# schematic.net
KiCad netlist of a schematic drawn in EAGLE
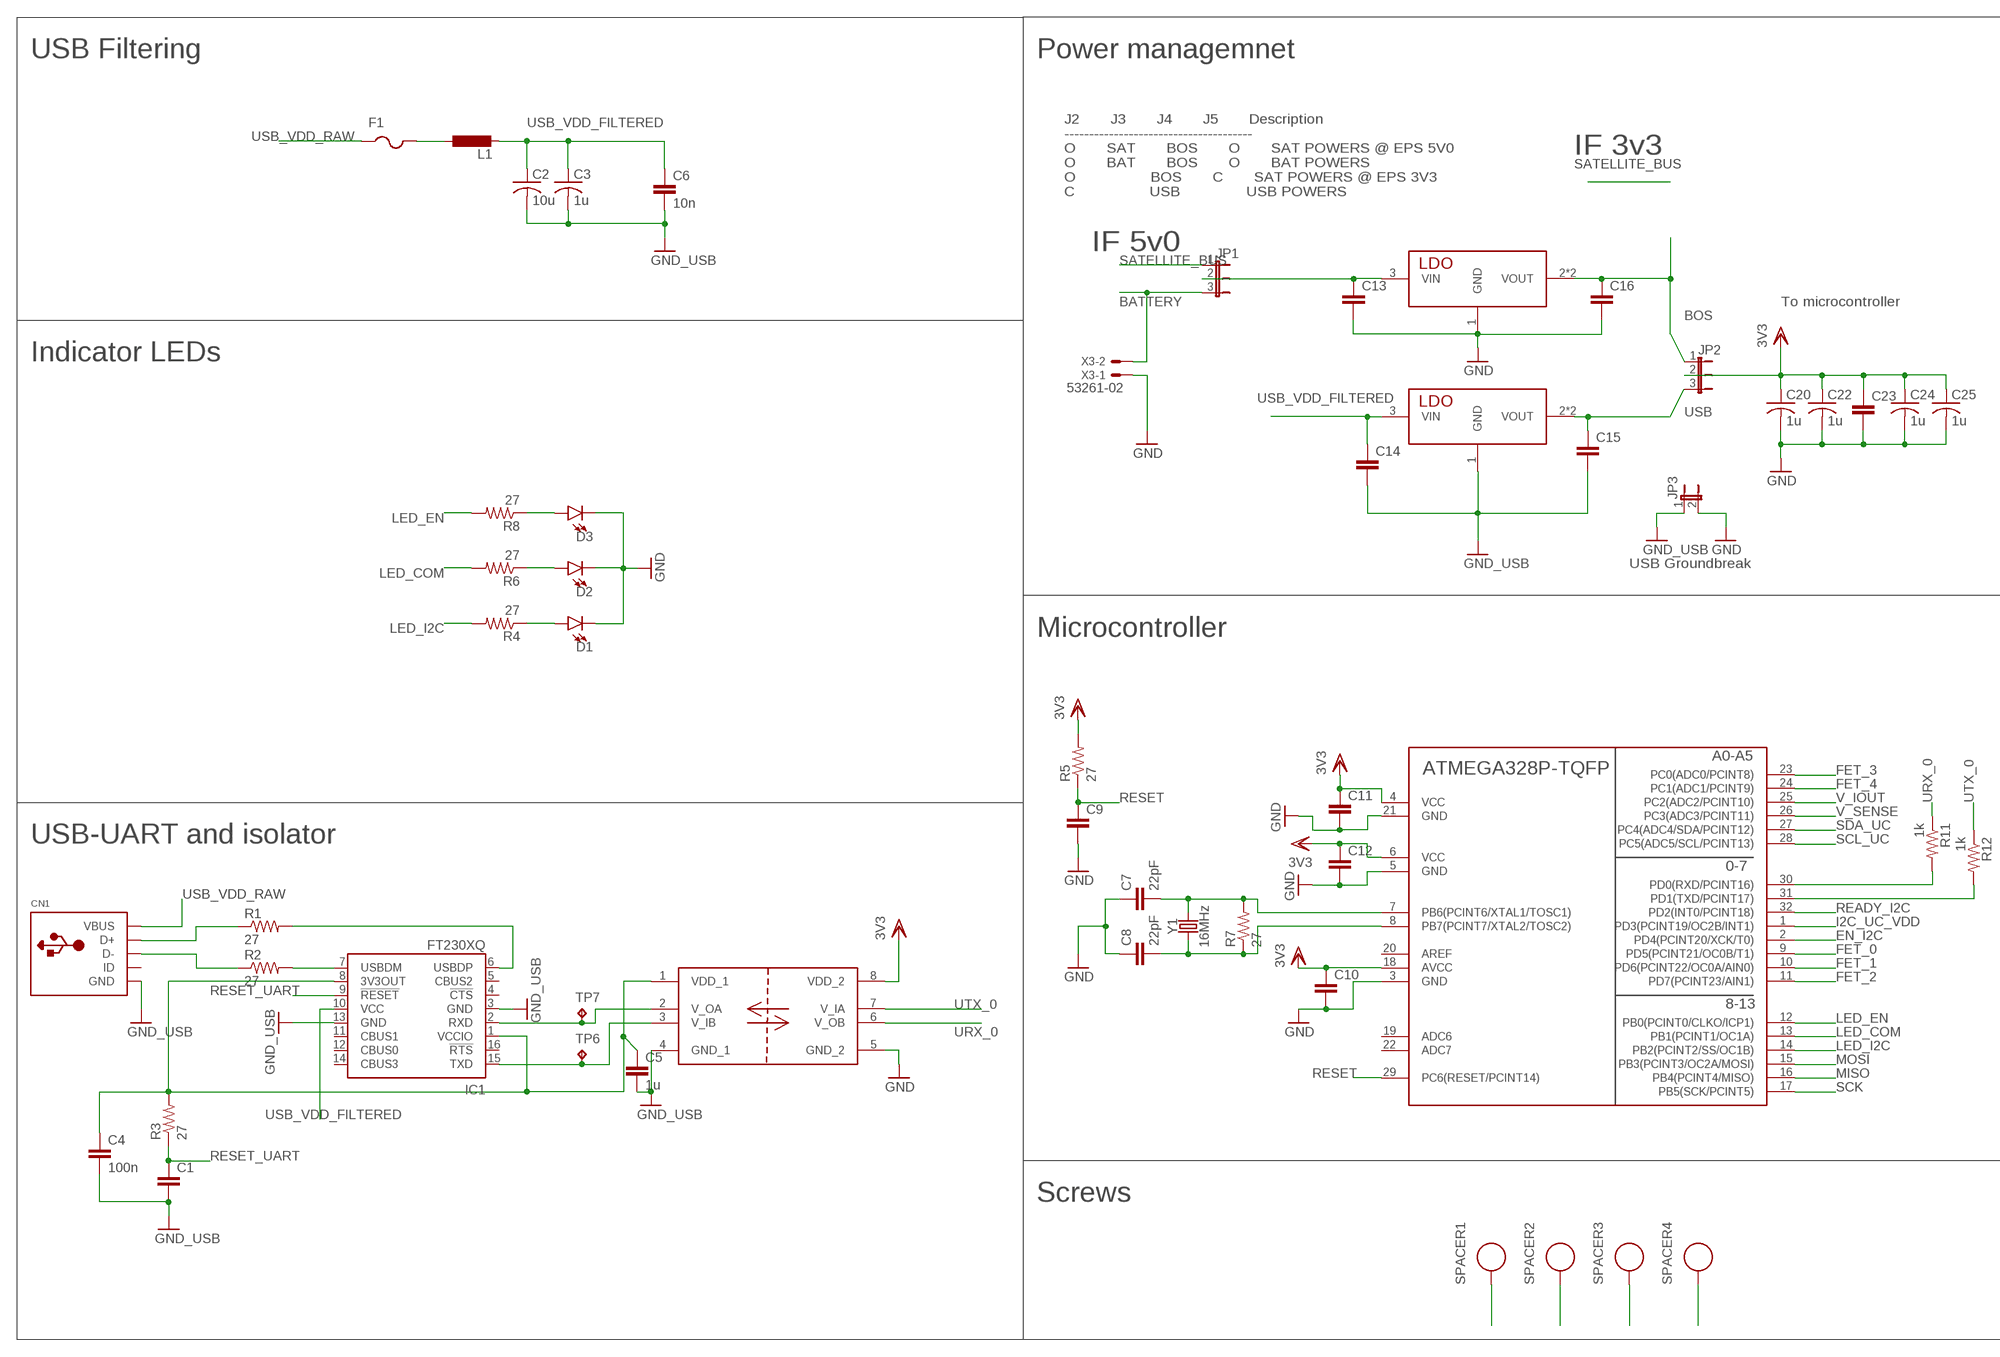
[diagram p0: schematic, sheet 1, part 1 of 2]
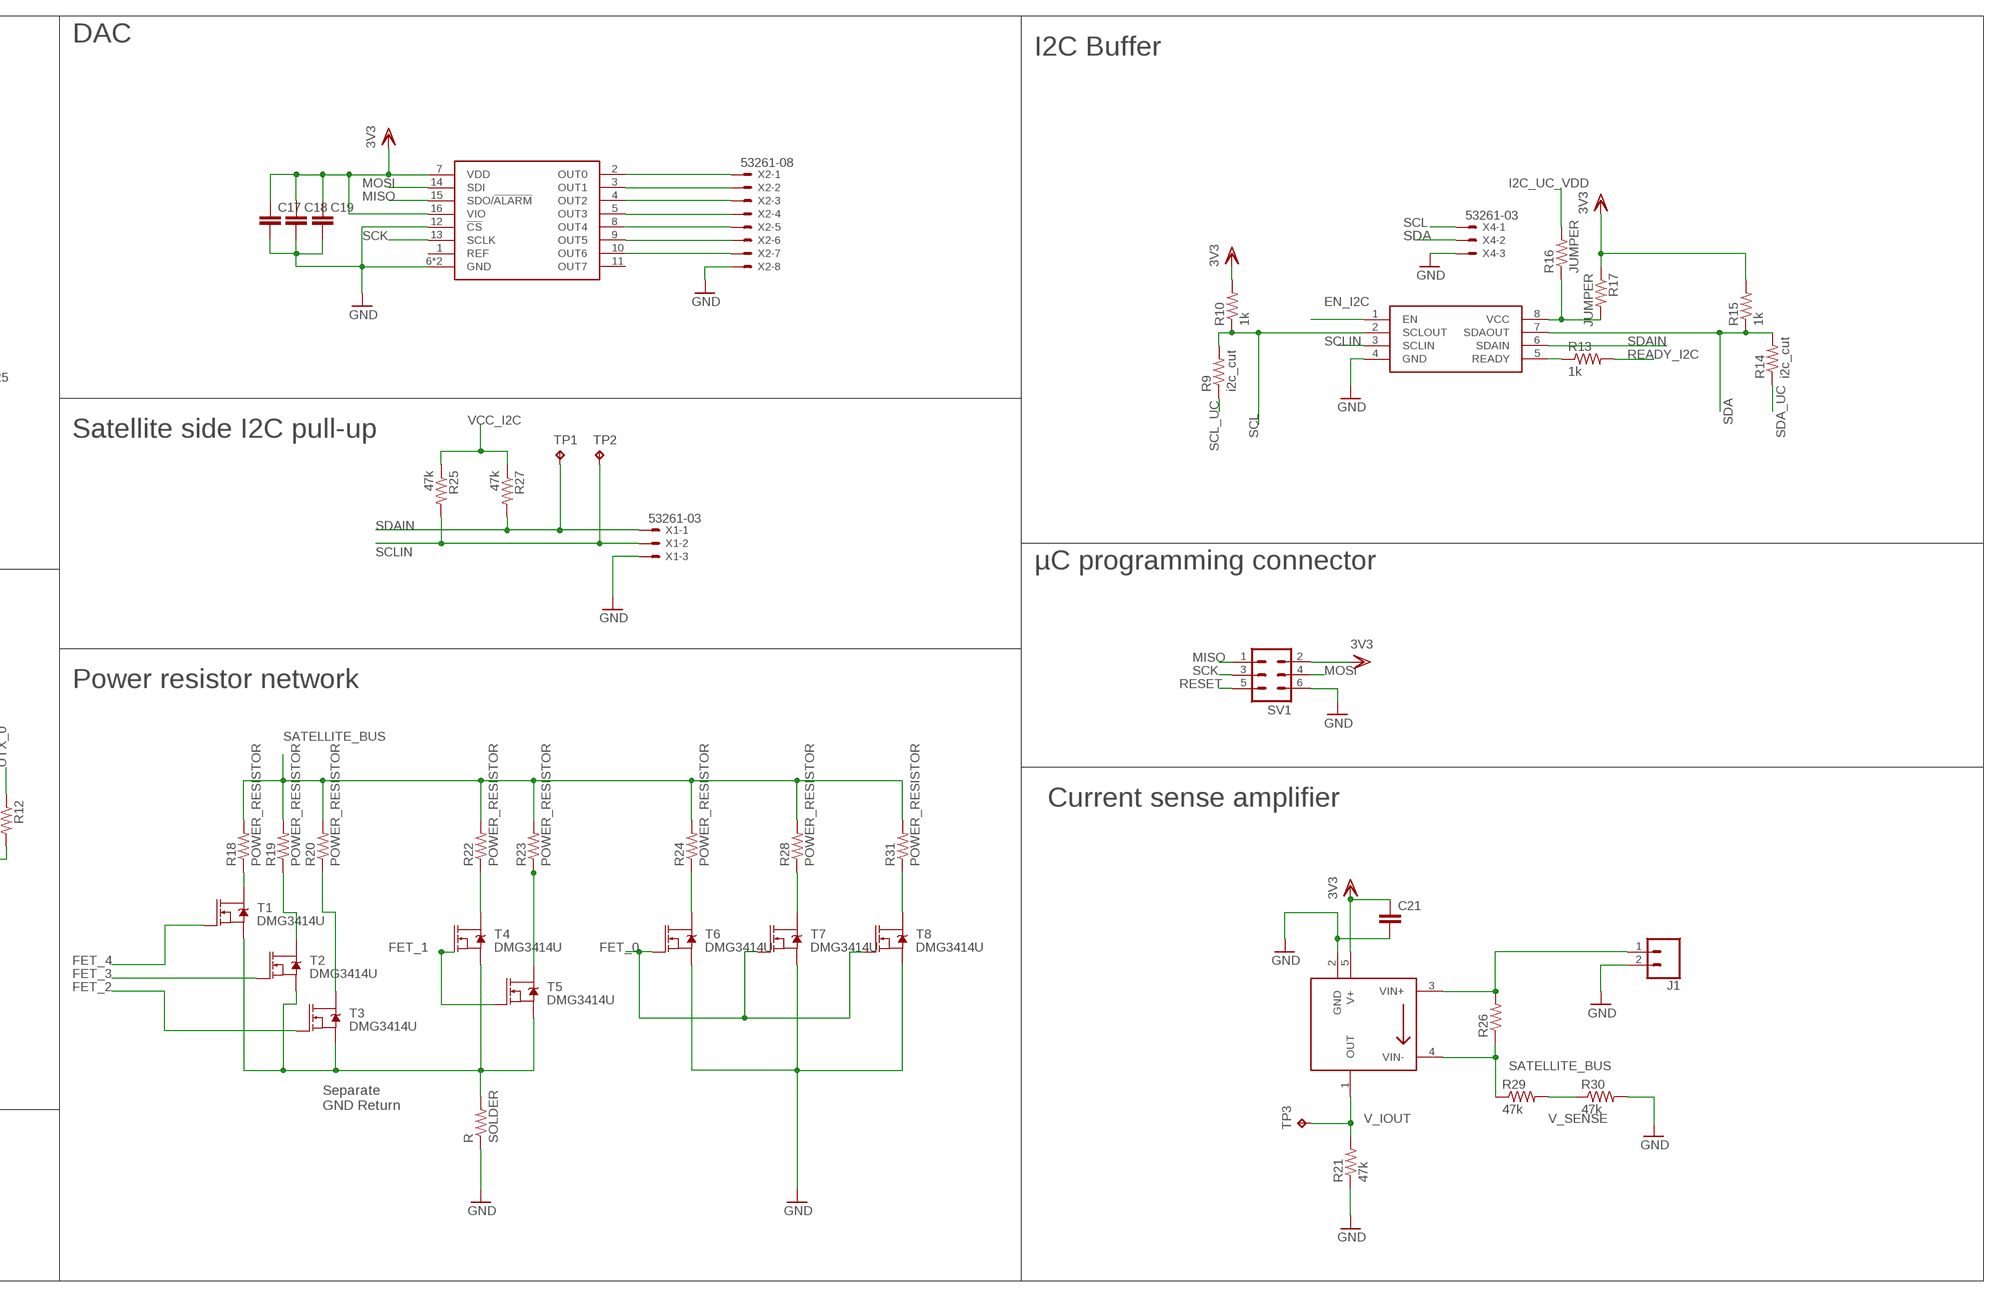
[diagram p1: schematic, sheet 1, part 2 of 2]

(export (version "E")
  (design (tool "Eeschema 10.0.6"))
  (components
    (comp (ref "C1")
      (value "C-EUC0603")
      (footprint "eagle-import:C0603")
      (libsource (lib "eagle-import") (part "C-EUC0603"))
    )
    (comp (ref "C2")
      (value "10u")
      (footprint "eagle-import:C3225")
      (libsource (lib "eagle-import") (part "C-USC3225"))
    )
    (comp (ref "C3")
      (value "1u")
      (footprint "eagle-import:C3225")
      (libsource (lib "eagle-import") (part "C-USC3225"))
    )
    (comp (ref "C4")
      (value "100n")
      (footprint "eagle-import:C0603")
      (libsource (lib "eagle-import") (part "C-EUC0603"))
    )
    (comp (ref "C5")
      (value "1u")
      (footprint "eagle-import:C0603")
      (libsource (lib "eagle-import") (part "C-EUC0603"))
    )
    (comp (ref "C6")
      (value "10n")
      (footprint "eagle-import:C0603")
      (libsource (lib "eagle-import") (part "C-EUC0603"))
    )
    (comp (ref "C7")
      (value "22pF")
      (footprint "eagle-import:C0603")
      (libsource (lib "eagle-import") (part "C-EUC0603"))
    )
    (comp (ref "C8")
      (value "22pF")
      (footprint "eagle-import:C0603")
      (libsource (lib "eagle-import") (part "C-EUC0603"))
    )
    (comp (ref "C9")
      (value "C-EUC0603")
      (footprint "eagle-import:C0603")
      (libsource (lib "eagle-import") (part "C-EUC0603"))
    )
    (comp (ref "C10")
      (value "C-EUC0603")
      (footprint "eagle-import:C0603")
      (libsource (lib "eagle-import") (part "C-EUC0603"))
    )
    (comp (ref "C11")
      (value "C-EUC0603")
      (footprint "eagle-import:C0603")
      (libsource (lib "eagle-import") (part "C-EUC0603"))
    )
    (comp (ref "C12")
      (value "C-EUC0603")
      (footprint "eagle-import:C0603")
      (libsource (lib "eagle-import") (part "C-EUC0603"))
    )
    (comp (ref "C13")
      (value "C-EUC0603")
      (footprint "eagle-import:C0603")
      (libsource (lib "eagle-import") (part "C-EUC0603"))
    )
    (comp (ref "C14")
      (value "C-EUC0603")
      (footprint "eagle-import:C0603")
      (libsource (lib "eagle-import") (part "C-EUC0603"))
    )
    (comp (ref "C15")
      (value "C-EUC0603")
      (footprint "eagle-import:C0603")
      (libsource (lib "eagle-import") (part "C-EUC0603"))
    )
    (comp (ref "C16")
      (value "C-EUC0603")
      (footprint "eagle-import:C0603")
      (libsource (lib "eagle-import") (part "C-EUC0603"))
    )
    (comp (ref "C17")
      (value "C-EUC0603")
      (footprint "eagle-import:C0603")
      (libsource (lib "eagle-import") (part "C-EUC0603"))
    )
    (comp (ref "C18")
      (value "C-EUC0603")
      (footprint "eagle-import:C0603")
      (libsource (lib "eagle-import") (part "C-EUC0603"))
    )
    (comp (ref "C19")
      (value "C-EUC0603")
      (footprint "eagle-import:C0603")
      (libsource (lib "eagle-import") (part "C-EUC0603"))
    )
    (comp (ref "C20")
      (value "1u")
      (footprint "eagle-import:C3225")
      (libsource (lib "eagle-import") (part "C-USC3225"))
    )
    (comp (ref "C21")
      (value "C-EUC0603")
      (footprint "eagle-import:C0603")
      (libsource (lib "eagle-import") (part "C-EUC0603"))
    )
    (comp (ref "C22")
      (value "1u")
      (footprint "eagle-import:C3225")
      (libsource (lib "eagle-import") (part "C-USC3225"))
    )
    (comp (ref "C23")
      (value "C-EUC0603")
      (footprint "eagle-import:C0603")
      (libsource (lib "eagle-import") (part "C-EUC0603"))
    )
    (comp (ref "C24")
      (value "1u")
      (footprint "eagle-import:C3225")
      (libsource (lib "eagle-import") (part "C-USC3225"))
    )
    (comp (ref "C25")
      (value "1u")
      (footprint "eagle-import:C3225")
      (libsource (lib "eagle-import") (part "C-USC3225"))
    )
    (comp (ref "CN1")
      (value "USBMINIB")
      (footprint "eagle-import:USB-MINIB")
      (libsource (lib "eagle-import") (part "USBMINIB"))
    )
    (comp (ref "D1")
      (value "LED0603")
      (footprint "eagle-import:LED-0603")
      (libsource (lib "eagle-import") (part "LED0603"))
    )
    (comp (ref "D2")
      (value "LED0603")
      (footprint "eagle-import:LED-0603")
      (libsource (lib "eagle-import") (part "LED0603"))
    )
    (comp (ref "D3")
      (value "LED0603")
      (footprint "eagle-import:LED-0603")
      (libsource (lib "eagle-import") (part "LED0603"))
    )
    (comp (ref "F1")
      (value "PTCFUSE-1812")
      (footprint "eagle-import:1812")
      (libsource (lib "eagle-import") (part "PTCFUSE-1812"))
    )
    (comp (ref "I1")
      (value "ADUM1201ARZ")
      (footprint "eagle-import:SO08")
      (libsource (lib "eagle-import") (part "ADUM1201ARZ"))
    )
    (comp (ref "I2")
      (value "LDL1117S33R")
      (footprint "eagle-import:SOT223")
      (libsource (lib "eagle-import") (part "LDL1117S33R"))
    )
    (comp (ref "I3")
      (value "LDL1117S33R")
      (footprint "eagle-import:SOT223")
      (libsource (lib "eagle-import") (part "LDL1117S33R"))
    )
    (comp (ref "I4")
      (value "ATMEGA328PCORRECT")
      (footprint "eagle-import:TQFP32-08")
      (libsource (lib "eagle-import") (part "ATMEGA328PCORRECT"))
    )
    (comp (ref "I5")
      (value "DAC70508MRTET")
      (footprint "eagle-import:QFN16-3X3MM")
      (libsource (lib "eagle-import") (part "DAC70508MRTET"))
    )
    (comp (ref "I6")
      (value "INA139")
      (footprint "eagle-import:DBV_R-PDSO-G5")
      (libsource (lib "eagle-import") (part "INA139"))
    )
    (comp (ref "IC1")
      (value "FT230XQ")
      (footprint "eagle-import:QFN16")
      (libsource (lib "eagle-import") (part "FT230XQ"))
    )
    (comp (ref "J1")
      (value "CONN_023.5MM")
      (footprint "eagle-import:SCREWTERMINAL-3.5MM-2")
      (libsource (lib "eagle-import") (part "CONN_023.5MM"))
    )
    (comp (ref "JP1")
      (value "JP2E")
      (footprint "eagle-import:JP2")
      (libsource (lib "eagle-import") (part "JP2E"))
    )
    (comp (ref "JP2")
      (value "JP2E")
      (footprint "eagle-import:JP2")
      (libsource (lib "eagle-import") (part "JP2E"))
    )
    (comp (ref "JP3")
      (value "JP1E")
      (footprint "eagle-import:JP1")
      (libsource (lib "eagle-import") (part "JP1E"))
    )
    (comp (ref "L1")
      (value "L-EUWE-TPC")
      (footprint "eagle-import:POWER-CHOKE_WE-TPC")
      (libsource (lib "eagle-import") (part "L-EUWE-TPC"))
    )
    (comp (ref "R")
      (value "SOLDER")
      (footprint "eagle-import:R0805")
      (libsource (lib "eagle-import") (part "R-US_R0805"))
    )
    (comp (ref "R1")
      (value "27")
      (footprint "eagle-import:R0603")
      (libsource (lib "eagle-import") (part "R-US_R0603"))
    )
    (comp (ref "R2")
      (value "27")
      (footprint "eagle-import:R0603")
      (libsource (lib "eagle-import") (part "R-US_R0603"))
    )
    (comp (ref "R3")
      (value "27")
      (footprint "eagle-import:R0603")
      (libsource (lib "eagle-import") (part "R-US_R0603"))
    )
    (comp (ref "R4")
      (value "27")
      (footprint "eagle-import:R0603")
      (libsource (lib "eagle-import") (part "R-US_R0603"))
    )
    (comp (ref "R5")
      (value "27")
      (footprint "eagle-import:R0603")
      (libsource (lib "eagle-import") (part "R-US_R0603"))
    )
    (comp (ref "R6")
      (value "27")
      (footprint "eagle-import:R0603")
      (libsource (lib "eagle-import") (part "R-US_R0603"))
    )
    (comp (ref "R7")
      (value "27")
      (footprint "eagle-import:R0603")
      (libsource (lib "eagle-import") (part "R-US_R0603"))
    )
    (comp (ref "R8")
      (value "27")
      (footprint "eagle-import:R0603")
      (libsource (lib "eagle-import") (part "R-US_R0603"))
    )
    (comp (ref "R9")
      (value "i2c_cut")
      (footprint "eagle-import:R0603")
      (libsource (lib "eagle-import") (part "R-US_R0603"))
    )
    (comp (ref "R10")
      (value "1k")
      (footprint "eagle-import:R0603")
      (libsource (lib "eagle-import") (part "R-US_R0603"))
    )
    (comp (ref "R11")
      (value "1k")
      (footprint "eagle-import:R0603")
      (libsource (lib "eagle-import") (part "R-US_R0603"))
    )
    (comp (ref "R12")
      (value "1k")
      (footprint "eagle-import:R0603")
      (libsource (lib "eagle-import") (part "R-US_R0603"))
    )
    (comp (ref "R13")
      (value "1k")
      (footprint "eagle-import:R0603")
      (libsource (lib "eagle-import") (part "R-US_R0603"))
    )
    (comp (ref "R14")
      (value "i2c_cut")
      (footprint "eagle-import:R0603")
      (libsource (lib "eagle-import") (part "R-US_R0603"))
    )
    (comp (ref "R15")
      (value "1k")
      (footprint "eagle-import:R0603")
      (libsource (lib "eagle-import") (part "R-US_R0603"))
    )
    (comp (ref "R16")
      (value "JUMPER")
      (footprint "eagle-import:R0603")
      (libsource (lib "eagle-import") (part "R-US_R0603"))
    )
    (comp (ref "R17")
      (value "JUMPER")
      (footprint "eagle-import:R0603")
      (libsource (lib "eagle-import") (part "R-US_R0603"))
    )
    (comp (ref "R18")
      (value "POWER_RESISTOR")
      (footprint "eagle-import:POWER_RESISTOR")
      (libsource (lib "eagle-import") (part "POWER_RESISTOR"))
    )
    (comp (ref "R19")
      (value "POWER_RESISTOR")
      (footprint "eagle-import:POWER_RESISTOR")
      (libsource (lib "eagle-import") (part "POWER_RESISTOR"))
    )
    (comp (ref "R20")
      (value "POWER_RESISTOR")
      (footprint "eagle-import:POWER_RESISTOR")
      (libsource (lib "eagle-import") (part "POWER_RESISTOR"))
    )
    (comp (ref "R21")
      (value "47k")
      (footprint "eagle-import:R0603")
      (libsource (lib "eagle-import") (part "R-US_R0603"))
    )
    (comp (ref "R22")
      (value "POWER_RESISTOR")
      (footprint "eagle-import:POWER_RESISTOR")
      (libsource (lib "eagle-import") (part "POWER_RESISTOR"))
    )
    (comp (ref "R23")
      (value "POWER_RESISTOR")
      (footprint "eagle-import:POWER_RESISTOR")
      (libsource (lib "eagle-import") (part "POWER_RESISTOR"))
    )
    (comp (ref "R24")
      (value "POWER_RESISTOR")
      (footprint "eagle-import:POWER_RESISTOR")
      (libsource (lib "eagle-import") (part "POWER_RESISTOR"))
    )
    (comp (ref "R25")
      (value "47k")
      (footprint "eagle-import:R0603")
      (libsource (lib "eagle-import") (part "R-US_R0603"))
    )
    (comp (ref "R26")
      (value "R-US_R0805")
      (footprint "eagle-import:R0805")
      (libsource (lib "eagle-import") (part "R-US_R0805"))
    )
    (comp (ref "R27")
      (value "47k")
      (footprint "eagle-import:R0603")
      (libsource (lib "eagle-import") (part "R-US_R0603"))
    )
    (comp (ref "R28")
      (value "POWER_RESISTOR")
      (footprint "eagle-import:POWER_RESISTOR")
      (libsource (lib "eagle-import") (part "POWER_RESISTOR"))
    )
    (comp (ref "R29")
      (value "47k")
      (footprint "eagle-import:R0603")
      (libsource (lib "eagle-import") (part "R-US_R0603"))
    )
    (comp (ref "R30")
      (value "47k")
      (footprint "eagle-import:R0603")
      (libsource (lib "eagle-import") (part "R-US_R0603"))
    )
    (comp (ref "R31")
      (value "POWER_RESISTOR")
      (footprint "eagle-import:POWER_RESISTOR")
      (libsource (lib "eagle-import") (part "POWER_RESISTOR"))
    )
    (comp (ref "SPACER1")
      (value "WA-SMSR_9775960")
      (footprint "eagle-import:WA-SMSR_9775______")
      (libsource (lib "eagle-import") (part "WA-SMSR_9775960"))
    )
    (comp (ref "SPACER2")
      (value "WA-SMSR_9775960")
      (footprint "eagle-import:WA-SMSR_9775______")
      (libsource (lib "eagle-import") (part "WA-SMSR_9775960"))
    )
    (comp (ref "SPACER3")
      (value "WA-SMSR_9775960")
      (footprint "eagle-import:WA-SMSR_9775______")
      (libsource (lib "eagle-import") (part "WA-SMSR_9775960"))
    )
    (comp (ref "SPACER4")
      (value "WA-SMSR_9775960")
      (footprint "eagle-import:WA-SMSR_9775______")
      (libsource (lib "eagle-import") (part "WA-SMSR_9775960"))
    )
    (comp (ref "SV1")
      (value "MA03-2")
      (footprint "eagle-import:MA03-2")
      (libsource (lib "eagle-import") (part "MA03-2"))
    )
    (comp (ref "T1")
      (value "DMG3414U")
      (footprint "eagle-import:SOT23-EBC")
      (libsource (lib "eagle-import") (part "DMG3414U"))
    )
    (comp (ref "T2")
      (value "DMG3414U")
      (footprint "eagle-import:SOT23-EBC")
      (libsource (lib "eagle-import") (part "DMG3414U"))
    )
    (comp (ref "T3")
      (value "DMG3414U")
      (footprint "eagle-import:SOT23-EBC")
      (libsource (lib "eagle-import") (part "DMG3414U"))
    )
    (comp (ref "T4")
      (value "DMG3414U")
      (footprint "eagle-import:SOT23-EBC")
      (libsource (lib "eagle-import") (part "DMG3414U"))
    )
    (comp (ref "T5")
      (value "DMG3414U")
      (footprint "eagle-import:SOT23-EBC")
      (libsource (lib "eagle-import") (part "DMG3414U"))
    )
    (comp (ref "T6")
      (value "DMG3414U")
      (footprint "eagle-import:SOT23-EBC")
      (libsource (lib "eagle-import") (part "DMG3414U"))
    )
    (comp (ref "T7")
      (value "DMG3414U")
      (footprint "eagle-import:SOT23-EBC")
      (libsource (lib "eagle-import") (part "DMG3414U"))
    )
    (comp (ref "T8")
      (value "DMG3414U")
      (footprint "eagle-import:SOT23-EBC")
      (libsource (lib "eagle-import") (part "DMG3414U"))
    )
    (comp (ref "TP1")
      (value "TPTP10R")
      (footprint "eagle-import:TP10R")
      (libsource (lib "eagle-import") (part "TPTP10R"))
    )
    (comp (ref "TP2")
      (value "TPTP10R")
      (footprint "eagle-import:TP10R")
      (libsource (lib "eagle-import") (part "TPTP10R"))
    )
    (comp (ref "TP3")
      (value "TPTP10R")
      (footprint "eagle-import:TP10R")
      (libsource (lib "eagle-import") (part "TPTP10R"))
    )
    (comp (ref "TP6")
      (value "TPTP10R")
      (footprint "eagle-import:TP10R")
      (libsource (lib "eagle-import") (part "TPTP10R"))
    )
    (comp (ref "TP7")
      (value "TPTP10R")
      (footprint "eagle-import:TP10R")
      (libsource (lib "eagle-import") (part "TPTP10R"))
    )
    (comp (ref "U1")
      (value "TCA4311A")
      (footprint "eagle-import:SSOP08")
      (libsource (lib "eagle-import") (part "TCA4311A"))
    )
    (comp (ref "X1")
      (value "53261-03")
      (footprint "eagle-import:53261-03")
      (fields (field (name "MF") "MOLEX") (field (name "MPN") "53261-0390"))
      (libsource (lib "eagle-import") (part "53?-03261"))
    )
    (comp (ref "X2")
      (value "53261-08")
      (footprint "eagle-import:53261-08")
      (fields (field (name "MF") "MOLEX"))
      (libsource (lib "eagle-import") (part "53?-08261"))
    )
    (comp (ref "X3")
      (value "53261-02")
      (footprint "eagle-import:53261-02")
      (fields (field (name "MF") "MOLEX"))
      (libsource (lib "eagle-import") (part "53?-02261"))
    )
    (comp (ref "X4")
      (value "53261-03")
      (footprint "eagle-import:53261-03")
      (fields (field (name "MF") "MOLEX") (field (name "MPN") "53261-0390"))
      (libsource (lib "eagle-import") (part "53?-03261"))
    )
    (comp (ref "Y1")
      (value "16MHz")
      (footprint "eagle-import:CRYSTAL-SMD-5X3.2-4PAD")
      (libsource (lib "eagle-import") (part "CRYSTAL-16MHZSMD-5X3.2"))
    )
  )
  (nets
    (net (code "1") (name "/BATTERY") (class "Default")
      (node (ref "JP1") (pin "3") (pinfunction "3_3") (pintype "passive"))
      (node (ref "X3") (pin "2") (pinfunction "S_2") (pintype "passive"))
    )
    (net (code "2") (name "/BOS") (class "Default")
      (node (ref "C16") (pin "1") (pinfunction "1_1") (pintype "passive"))
      (node (ref "I2") (pin "2") (pinfunction "VOUT_2") (pintype "bidirectional"))
      (node (ref "I2") (pin "2*2") (pinfunction "VOUT_2*2") (pintype "bidirectional"))
      (node (ref "JP2") (pin "1") (pinfunction "1_1") (pintype "passive"))
    )
    (net (code "3") (name "/EN_I2C") (class "Default")
      (node (ref "I4") (pin "2") (pinfunction "PD4(PCINT20/XCK/T0)_2") (pintype "bidirectional"))
      (node (ref "U1") (pin "1") (pinfunction "EN_1") (pintype "bidirectional"))
    )
    (net (code "4") (name "/FET_0") (class "Default")
      (node (ref "I4") (pin "9") (pinfunction "PD5(PCINT21/OC0B/T1)_9") (pintype "bidirectional"))
      (node (ref "T6") (pin "G") (pinfunction "G_G") (pintype "bidirectional"))
      (node (ref "T7") (pin "G") (pinfunction "G_G") (pintype "bidirectional"))
      (node (ref "T8") (pin "G") (pinfunction "G_G") (pintype "bidirectional"))
    )
    (net (code "5") (name "/FET_1") (class "Default")
      (node (ref "I4") (pin "10") (pinfunction "PD6(PCINT22/OC0A/AIN0)_10") (pintype "bidirectional"))
      (node (ref "T4") (pin "G") (pinfunction "G_G") (pintype "bidirectional"))
      (node (ref "T5") (pin "G") (pinfunction "G_G") (pintype "bidirectional"))
    )
    (net (code "6") (name "/FET_2") (class "Default")
      (node (ref "I4") (pin "11") (pinfunction "PD7(PCINT23/AIN1)_11") (pintype "bidirectional"))
      (node (ref "T3") (pin "G") (pinfunction "G_G") (pintype "bidirectional"))
    )
    (net (code "7") (name "/FET_3") (class "Default")
      (node (ref "I4") (pin "23") (pinfunction "PC0(ADC0/PCINT8)_23") (pintype "bidirectional"))
      (node (ref "T2") (pin "G") (pinfunction "G_G") (pintype "bidirectional"))
    )
    (net (code "8") (name "/FET_4") (class "Default")
      (node (ref "I4") (pin "24") (pinfunction "PC1(ADC1/PCINT9)_24") (pintype "bidirectional"))
      (node (ref "T1") (pin "G") (pinfunction "G_G") (pintype "bidirectional"))
    )
    (net (code "9") (name "/I2C_UC_VDD") (class "Default")
      (node (ref "I4") (pin "1") (pinfunction "PD3(PCINT19/OC2B/INT1)_1") (pintype "bidirectional"))
      (node (ref "R16") (pin "2") (pinfunction "2_2") (pintype "passive"))
    )
    (net (code "10") (name "/LED_COM") (class "Default")
      (node (ref "I4") (pin "13") (pinfunction "PB1(PCINT1/OC1A)_13") (pintype "bidirectional"))
      (node (ref "R6") (pin "2") (pinfunction "2_2") (pintype "passive"))
    )
    (net (code "11") (name "/LED_EN") (class "Default")
      (node (ref "I4") (pin "12") (pinfunction "PB0(PCINT0/CLKO/ICP1)_12") (pintype "bidirectional"))
      (node (ref "R8") (pin "2") (pinfunction "2_2") (pintype "passive"))
    )
    (net (code "12") (name "/LED_I2C") (class "Default")
      (node (ref "I4") (pin "14") (pinfunction "PB2(PCINT2/SS/OC1B)_14") (pintype "bidirectional"))
      (node (ref "R4") (pin "2") (pinfunction "2_2") (pintype "passive"))
    )
    (net (code "13") (name "/MISO") (class "Default")
      (node (ref "I4") (pin "16") (pinfunction "PB4(PCINT4/MISO)_16") (pintype "bidirectional"))
      (node (ref "I5") (pin "15") (pinfunction "SDO/~{ALARM}_15") (pintype "bidirectional"))
      (node (ref "SV1") (pin "1") (pinfunction "1_1") (pintype "passive"))
    )
    (net (code "14") (name "/MOSI") (class "Default")
      (node (ref "I4") (pin "15") (pinfunction "PB3(PCINT3/OC2A/MOSI)_15") (pintype "bidirectional"))
      (node (ref "I5") (pin "14") (pinfunction "SDI_14") (pintype "bidirectional"))
      (node (ref "SV1") (pin "4") (pinfunction "4_4") (pintype "passive"))
    )
    (net (code "15") (name "/READY_I2C") (class "Default")
      (node (ref "I4") (pin "32") (pinfunction "PD2(INT0/PCINT18)_32") (pintype "bidirectional"))
      (node (ref "R13") (pin "2") (pinfunction "2_2") (pintype "passive"))
    )
    (net (code "16") (name "/RESET") (class "Default")
      (node (ref "C9") (pin "1") (pinfunction "1_1") (pintype "passive"))
      (node (ref "I4") (pin "29") (pinfunction "PC6(RESET/PCINT14)_29") (pintype "bidirectional"))
      (node (ref "R5") (pin "1") (pinfunction "1_1") (pintype "passive"))
      (node (ref "SV1") (pin "5") (pinfunction "5_5") (pintype "passive"))
    )
    (net (code "17") (name "/RESET_UART") (class "Default")
      (node (ref "C1") (pin "1") (pinfunction "1_1") (pintype "passive"))
      (node (ref "IC1") (pin "9") (pinfunction "~{RESET}_9") (pintype "input"))
      (node (ref "R3") (pin "1") (pinfunction "1_1") (pintype "passive"))
    )
    (net (code "18") (name "/SATELLITE_BUS") (class "Default")
      (node (ref "I6") (pin "4") (pinfunction "VIN-_4") (pintype "bidirectional"))
      (node (ref "JP1") (pin "1") (pinfunction "1_1") (pintype "passive"))
      (node (ref "R18") (pin "P$3") (pinfunction "2_P$3") (pintype "passive"))
      (node (ref "R19") (pin "P$3") (pinfunction "2_P$3") (pintype "passive"))
      (node (ref "R20") (pin "P$3") (pinfunction "2_P$3") (pintype "passive"))
      (node (ref "R22") (pin "P$3") (pinfunction "2_P$3") (pintype "passive"))
      (node (ref "R23") (pin "P$3") (pinfunction "2_P$3") (pintype "passive"))
      (node (ref "R24") (pin "P$3") (pinfunction "2_P$3") (pintype "passive"))
      (node (ref "R26") (pin "1") (pinfunction "1_1") (pintype "passive"))
      (node (ref "R28") (pin "P$3") (pinfunction "2_P$3") (pintype "passive"))
      (node (ref "R29") (pin "1") (pinfunction "1_1") (pintype "passive"))
      (node (ref "R31") (pin "P$3") (pinfunction "2_P$3") (pintype "passive"))
    )
    (net (code "19") (name "/SCK") (class "Default")
      (node (ref "I4") (pin "17") (pinfunction "PB5(SCK/PCINT5)_17") (pintype "bidirectional"))
      (node (ref "I5") (pin "13") (pinfunction "SCLK_13") (pintype "bidirectional"))
      (node (ref "SV1") (pin "3") (pinfunction "3_3") (pintype "passive"))
    )
    (net (code "20") (name "/SCL") (class "Default")
      (node (ref "R10") (pin "1") (pinfunction "1_1") (pintype "passive"))
      (node (ref "R9") (pin "2") (pinfunction "2_2") (pintype "passive"))
      (node (ref "U1") (pin "2") (pinfunction "SCLOUT_2") (pintype "bidirectional"))
      (node (ref "X4") (pin "1") (pinfunction "S_1") (pintype "passive"))
    )
    (net (code "21") (name "/SCLIN") (class "Default")
      (node (ref "R25") (pin "2") (pinfunction "2_2") (pintype "passive"))
      (node (ref "TP2") (pin "TP") (pinfunction "TP_TP") (pintype "input"))
      (node (ref "U1") (pin "3") (pinfunction "SCLIN_3") (pintype "bidirectional"))
      (node (ref "X1") (pin "2") (pinfunction "S_2") (pintype "passive"))
    )
    (net (code "22") (name "/SCL_UC") (class "Default")
      (node (ref "I4") (pin "28") (pinfunction "PC5(ADC5/SCL/PCINT13)_28") (pintype "bidirectional"))
      (node (ref "R9") (pin "1") (pinfunction "1_1") (pintype "passive"))
    )
    (net (code "23") (name "/SDA") (class "Default")
      (node (ref "R14") (pin "2") (pinfunction "2_2") (pintype "passive"))
      (node (ref "R15") (pin "1") (pinfunction "1_1") (pintype "passive"))
      (node (ref "U1") (pin "7") (pinfunction "SDAOUT_7") (pintype "bidirectional"))
      (node (ref "X4") (pin "2") (pinfunction "S_2") (pintype "passive"))
    )
    (net (code "24") (name "/SDAIN") (class "Default")
      (node (ref "R27") (pin "2") (pinfunction "2_2") (pintype "passive"))
      (node (ref "TP1") (pin "TP") (pinfunction "TP_TP") (pintype "input"))
      (node (ref "U1") (pin "6") (pinfunction "SDAIN_6") (pintype "bidirectional"))
      (node (ref "X1") (pin "1") (pinfunction "S_1") (pintype "passive"))
    )
    (net (code "25") (name "/SDA_UC") (class "Default")
      (node (ref "I4") (pin "27") (pinfunction "PC4(ADC4/SDA/PCINT12)_27") (pintype "bidirectional"))
      (node (ref "R14") (pin "1") (pinfunction "1_1") (pintype "passive"))
    )
    (net (code "26") (name "/URX_0") (class "Default")
      (node (ref "I1") (pin "6") (pinfunction "V_OB_6") (pintype "bidirectional"))
      (node (ref "R11") (pin "1") (pinfunction "1_1") (pintype "passive"))
    )
    (net (code "27") (name "/USB") (class "Default")
      (node (ref "C15") (pin "1") (pinfunction "1_1") (pintype "passive"))
      (node (ref "I3") (pin "2") (pinfunction "VOUT_2") (pintype "bidirectional"))
      (node (ref "I3") (pin "2*2") (pinfunction "VOUT_2*2") (pintype "bidirectional"))
      (node (ref "JP2") (pin "3") (pinfunction "3_3") (pintype "passive"))
    )
    (net (code "28") (name "/USB_VDD_FILTERED") (class "Default")
      (node (ref "C14") (pin "1") (pinfunction "1_1") (pintype "passive"))
      (node (ref "C2") (pin "1") (pinfunction "1_1") (pintype "passive"))
      (node (ref "C3") (pin "1") (pinfunction "1_1") (pintype "passive"))
      (node (ref "C6") (pin "1") (pinfunction "1_1") (pintype "passive"))
      (node (ref "I3") (pin "3") (pinfunction "VIN_3") (pintype "bidirectional"))
      (node (ref "IC1") (pin "10") (pinfunction "VCC_10") (pintype "power_in"))
      (node (ref "L1") (pin "2") (pinfunction "2_2") (pintype "passive"))
    )
    (net (code "29") (name "/USB_VDD_RAW") (class "Default")
      (node (ref "CN1") (pin "VBUS") (pinfunction "VBUS_VBUS") (pintype "power_in"))
      (node (ref "F1") (pin "1") (pinfunction "1_1") (pintype "passive"))
    )
    (net (code "30") (name "/UTX_0") (class "Default")
      (node (ref "I1") (pin "7") (pinfunction "V_IA_7") (pintype "bidirectional"))
      (node (ref "R12") (pin "1") (pinfunction "1_1") (pintype "passive"))
    )
    (net (code "31") (name "/VCC_I2C") (class "Default")
      (node (ref "R16") (pin "1") (pinfunction "1_1") (pintype "passive"))
      (node (ref "R17") (pin "2") (pinfunction "2_2") (pintype "passive"))
      (node (ref "R25") (pin "1") (pinfunction "1_1") (pintype "passive"))
      (node (ref "R27") (pin "1") (pinfunction "1_1") (pintype "passive"))
      (node (ref "U1") (pin "8") (pinfunction "VCC_8") (pintype "bidirectional"))
    )
    (net (code "32") (name "/V_IOUT") (class "Default")
      (node (ref "I4") (pin "25") (pinfunction "PC2(ADC2/PCINT10)_25") (pintype "bidirectional"))
      (node (ref "I6") (pin "1") (pinfunction "OUT_1") (pintype "bidirectional"))
      (node (ref "R21") (pin "2") (pinfunction "2_2") (pintype "passive"))
      (node (ref "TP3") (pin "TP") (pinfunction "TP_TP") (pintype "input"))
    )
    (net (code "33") (name "/V_SENSE") (class "Default")
      (node (ref "I4") (pin "26") (pinfunction "PC3(ADC3/PCINT11)_26") (pintype "bidirectional"))
      (node (ref "R29") (pin "2") (pinfunction "2_2") (pintype "passive"))
      (node (ref "R30") (pin "1") (pinfunction "1_1") (pintype "passive"))
    )
    (net (code "34") (name "3V3") (class "Default")
      (node (ref "C10") (pin "1") (pinfunction "1_1") (pintype "passive"))
      (node (ref "C11") (pin "1") (pinfunction "1_1") (pintype "passive"))
      (node (ref "C12") (pin "1") (pinfunction "1_1") (pintype "passive"))
      (node (ref "C17") (pin "1") (pinfunction "1_1") (pintype "passive"))
      (node (ref "C18") (pin "1") (pinfunction "1_1") (pintype "passive"))
      (node (ref "C19") (pin "1") (pinfunction "1_1") (pintype "passive"))
      (node (ref "C20") (pin "1") (pinfunction "1_1") (pintype "passive"))
      (node (ref "C21") (pin "1") (pinfunction "1_1") (pintype "passive"))
      (node (ref "C22") (pin "1") (pinfunction "1_1") (pintype "passive"))
      (node (ref "C23") (pin "1") (pinfunction "1_1") (pintype "passive"))
      (node (ref "C24") (pin "1") (pinfunction "1_1") (pintype "passive"))
      (node (ref "C25") (pin "1") (pinfunction "1_1") (pintype "passive"))
      (node (ref "I1") (pin "8") (pinfunction "VDD_2_8") (pintype "bidirectional"))
      (node (ref "I4") (pin "18") (pinfunction "AVCC_18") (pintype "bidirectional"))
      (node (ref "I4") (pin "4") (pinfunction "VCC_4") (pintype "bidirectional"))
      (node (ref "I4") (pin "6") (pinfunction "VCC_6") (pintype "bidirectional"))
      (node (ref "I5") (pin "16") (pinfunction "VIO_16") (pintype "bidirectional"))
      (node (ref "I5") (pin "7") (pinfunction "VDD_7") (pintype "bidirectional"))
      (node (ref "I6") (pin "5") (pinfunction "V+_5") (pintype "bidirectional"))
      (node (ref "JP2") (pin "2") (pinfunction "2_2") (pintype "passive"))
      (node (ref "R10") (pin "2") (pinfunction "2_2") (pintype "passive"))
      (node (ref "R15") (pin "2") (pinfunction "2_2") (pintype "passive"))
      (node (ref "R17") (pin "1") (pinfunction "1_1") (pintype "passive"))
      (node (ref "R5") (pin "2") (pinfunction "2_2") (pintype "passive"))
      (node (ref "SV1") (pin "2") (pinfunction "2_2") (pintype "passive"))
    )
    (net (code "35") (name "GND") (class "Default")
      (node (ref "C10") (pin "2") (pinfunction "2_2") (pintype "passive"))
      (node (ref "C11") (pin "2") (pinfunction "2_2") (pintype "passive"))
      (node (ref "C12") (pin "2") (pinfunction "2_2") (pintype "passive"))
      (node (ref "C13") (pin "2") (pinfunction "2_2") (pintype "passive"))
      (node (ref "C16") (pin "2") (pinfunction "2_2") (pintype "passive"))
      (node (ref "C17") (pin "2") (pinfunction "2_2") (pintype "passive"))
      (node (ref "C18") (pin "2") (pinfunction "2_2") (pintype "passive"))
      (node (ref "C19") (pin "2") (pinfunction "2_2") (pintype "passive"))
      (node (ref "C20") (pin "2") (pinfunction "2_2") (pintype "passive"))
      (node (ref "C21") (pin "2") (pinfunction "2_2") (pintype "passive"))
      (node (ref "C22") (pin "2") (pinfunction "2_2") (pintype "passive"))
      (node (ref "C23") (pin "2") (pinfunction "2_2") (pintype "passive"))
      (node (ref "C24") (pin "2") (pinfunction "2_2") (pintype "passive"))
      (node (ref "C25") (pin "2") (pinfunction "2_2") (pintype "passive"))
      (node (ref "C7") (pin "1") (pinfunction "1_1") (pintype "passive"))
      (node (ref "C8") (pin "1") (pinfunction "1_1") (pintype "passive"))
      (node (ref "C9") (pin "2") (pinfunction "2_2") (pintype "passive"))
      (node (ref "D1") (pin "C") (pinfunction "C_C") (pintype "passive"))
      (node (ref "D2") (pin "C") (pinfunction "C_C") (pintype "passive"))
      (node (ref "D3") (pin "C") (pinfunction "C_C") (pintype "passive"))
      (node (ref "I1") (pin "5") (pinfunction "GND_2_5") (pintype "bidirectional"))
      (node (ref "I2") (pin "1") (pinfunction "GND_1") (pintype "bidirectional"))
      (node (ref "I4") (pin "21") (pinfunction "GND_21") (pintype "bidirectional"))
      (node (ref "I4") (pin "3") (pinfunction "GND_3") (pintype "bidirectional"))
      (node (ref "I4") (pin "5") (pinfunction "GND_5") (pintype "bidirectional"))
      (node (ref "I5") (pin "12") (pinfunction "~{CS}_12") (pintype "bidirectional"))
      (node (ref "I5") (pin "6") (pinfunction "GND_6") (pintype "bidirectional"))
      (node (ref "I5") (pin "EXT") (pinfunction "GND_EXT") (pintype "bidirectional"))
      (node (ref "I6") (pin "2") (pinfunction "GND_2") (pintype "bidirectional"))
      (node (ref "J1") (pin "2") (pinfunction "2_2") (pintype "passive"))
      (node (ref "JP3") (pin "2") (pinfunction "2_2") (pintype "passive"))
      (node (ref "R") (pin "1") (pinfunction "1_1") (pintype "passive"))
      (node (ref "R21") (pin "1") (pinfunction "1_1") (pintype "passive"))
      (node (ref "R30") (pin "2") (pinfunction "2_2") (pintype "passive"))
      (node (ref "SV1") (pin "6") (pinfunction "6_6") (pintype "passive"))
      (node (ref "T6") (pin "S") (pinfunction "S_S") (pintype "bidirectional"))
      (node (ref "T7") (pin "S") (pinfunction "S_S") (pintype "bidirectional"))
      (node (ref "T8") (pin "S") (pinfunction "S_S") (pintype "bidirectional"))
      (node (ref "U1") (pin "4") (pinfunction "GND_4") (pintype "bidirectional"))
      (node (ref "X1") (pin "3") (pinfunction "S_3") (pintype "passive"))
      (node (ref "X2") (pin "8") (pinfunction "S_8") (pintype "passive"))
      (node (ref "X3") (pin "1") (pinfunction "S_1") (pintype "passive"))
      (node (ref "X4") (pin "3") (pinfunction "S_3") (pintype "passive"))
    )
    (net (code "36") (name "GND_USB") (class "Default")
      (node (ref "C1") (pin "2") (pinfunction "2_2") (pintype "passive"))
      (node (ref "C14") (pin "2") (pinfunction "2_2") (pintype "passive"))
      (node (ref "C15") (pin "2") (pinfunction "2_2") (pintype "passive"))
      (node (ref "C2") (pin "2") (pinfunction "2_2") (pintype "passive"))
      (node (ref "C3") (pin "2") (pinfunction "2_2") (pintype "passive"))
      (node (ref "C4") (pin "2") (pinfunction "2_2") (pintype "passive"))
      (node (ref "C5") (pin "2") (pinfunction "2_2") (pintype "passive"))
      (node (ref "C6") (pin "2") (pinfunction "2_2") (pintype "passive"))
      (node (ref "CN1") (pin "GND") (pinfunction "GND_GND") (pintype "power_in"))
      (node (ref "I1") (pin "4") (pinfunction "GND_1_4") (pintype "bidirectional"))
      (node (ref "I3") (pin "1") (pinfunction "GND_1") (pintype "bidirectional"))
      (node (ref "IC1") (pin "13") (pinfunction "GND_13") (pintype "power_in"))
      (node (ref "IC1") (pin "3") (pinfunction "GND_3") (pintype "power_in"))
      (node (ref "JP3") (pin "1") (pinfunction "1_1") (pintype "passive"))
    )
    (net (code "37") (name "Net-(CN1-PadD+)") (class "Default")
      (node (ref "CN1") (pin "D+") (pinfunction "D+_D+") (pintype "bidirectional"))
      (node (ref "R1") (pin "1") (pinfunction "1_1") (pintype "passive"))
    )
    (net (code "38") (name "Net-(CN1-PadD-)") (class "Default")
      (node (ref "CN1") (pin "D-") (pinfunction "D-_D-") (pintype "bidirectional"))
      (node (ref "R2") (pin "1") (pinfunction "1_1") (pintype "passive"))
    )
    (net (code "39") (name "Net-(D1-PadA)") (class "Default")
      (node (ref "D1") (pin "A") (pinfunction "A_A") (pintype "passive"))
      (node (ref "R4") (pin "1") (pinfunction "1_1") (pintype "passive"))
    )
    (net (code "40") (name "Net-(D2-PadA)") (class "Default")
      (node (ref "D2") (pin "A") (pinfunction "A_A") (pintype "passive"))
      (node (ref "R6") (pin "1") (pinfunction "1_1") (pintype "passive"))
    )
    (net (code "41") (name "Net-(D3-PadA)") (class "Default")
      (node (ref "D3") (pin "A") (pinfunction "A_A") (pintype "passive"))
      (node (ref "R8") (pin "1") (pinfunction "1_1") (pintype "passive"))
    )
    (net (code "42") (name "Net-(F1-Pad2)") (class "Default")
      (node (ref "F1") (pin "2") (pinfunction "2_2") (pintype "passive"))
      (node (ref "L1") (pin "1") (pinfunction "1_1") (pintype "passive"))
    )
    (net (code "43") (name "Net-(I1-VDD_1)") (class "Default")
      (node (ref "C4") (pin "1") (pinfunction "1_1") (pintype "passive"))
      (node (ref "C5") (pin "1") (pinfunction "1_1") (pintype "passive"))
      (node (ref "I1") (pin "1") (pinfunction "VDD_1_1") (pintype "bidirectional"))
      (node (ref "IC1") (pin "1") (pinfunction "VCCIO_1") (pintype "power_in"))
      (node (ref "IC1") (pin "8") (pinfunction "3V3OUT_8") (pintype "output"))
      (node (ref "R3") (pin "2") (pinfunction "2_2") (pintype "passive"))
    )
    (net (code "44") (name "Net-(I1-V_IB)") (class "Default")
      (node (ref "I1") (pin "3") (pinfunction "V_IB_3") (pintype "bidirectional"))
      (node (ref "IC1") (pin "15") (pinfunction "TXD_15") (pintype "output"))
      (node (ref "TP6") (pin "TP") (pinfunction "TP_TP") (pintype "input"))
    )
    (net (code "45") (name "Net-(I1-V_OA)") (class "Default")
      (node (ref "I1") (pin "2") (pinfunction "V_OA_2") (pintype "bidirectional"))
      (node (ref "IC1") (pin "2") (pinfunction "RXD_2") (pintype "input"))
      (node (ref "TP7") (pin "TP") (pinfunction "TP_TP") (pintype "input"))
    )
    (net (code "46") (name "Net-(I2-VIN)") (class "Default")
      (node (ref "C13") (pin "1") (pinfunction "1_1") (pintype "passive"))
      (node (ref "I2") (pin "3") (pinfunction "VIN_3") (pintype "bidirectional"))
      (node (ref "JP1") (pin "2") (pinfunction "2_2") (pintype "passive"))
    )
    (net (code "47") (name "Net-(I4-PB6(PCINT6{slash}XTAL1{slash}TOSC1))") (class "Default")
      (node (ref "C7") (pin "2") (pinfunction "2_2") (pintype "passive"))
      (node (ref "I4") (pin "7") (pinfunction "PB6(PCINT6/XTAL1/TOSC1)_7") (pintype "bidirectional"))
      (node (ref "R7") (pin "2") (pinfunction "2_2") (pintype "passive"))
      (node (ref "Y1") (pin "3") (pinfunction "2_3") (pintype "passive"))
    )
    (net (code "48") (name "Net-(I4-PB7(PCINT7{slash}XTAL2{slash}TOSC2))") (class "Default")
      (node (ref "C8") (pin "2") (pinfunction "2_2") (pintype "passive"))
      (node (ref "I4") (pin "8") (pinfunction "PB7(PCINT7/XTAL2/TOSC2)_8") (pintype "bidirectional"))
      (node (ref "R7") (pin "1") (pinfunction "1_1") (pintype "passive"))
      (node (ref "Y1") (pin "1") (pinfunction "1_1") (pintype "passive"))
    )
    (net (code "49") (name "Net-(I4-PD0(RXD{slash}PCINT16))") (class "Default")
      (node (ref "I4") (pin "30") (pinfunction "PD0(RXD/PCINT16)_30") (pintype "bidirectional"))
      (node (ref "R11") (pin "2") (pinfunction "2_2") (pintype "passive"))
    )
    (net (code "50") (name "Net-(I4-PD1(TXD{slash}PCINT17))") (class "Default")
      (node (ref "I4") (pin "31") (pinfunction "PD1(TXD/PCINT17)_31") (pintype "bidirectional"))
      (node (ref "R12") (pin "2") (pinfunction "2_2") (pintype "passive"))
    )
    (net (code "51") (name "Net-(I5-OUT0)") (class "Default")
      (node (ref "I5") (pin "2") (pinfunction "OUT0_2") (pintype "bidirectional"))
      (node (ref "X2") (pin "1") (pinfunction "S_1") (pintype "passive"))
    )
    (net (code "52") (name "Net-(I5-OUT1)") (class "Default")
      (node (ref "I5") (pin "3") (pinfunction "OUT1_3") (pintype "bidirectional"))
      (node (ref "X2") (pin "2") (pinfunction "S_2") (pintype "passive"))
    )
    (net (code "53") (name "Net-(I5-OUT2)") (class "Default")
      (node (ref "I5") (pin "4") (pinfunction "OUT2_4") (pintype "bidirectional"))
      (node (ref "X2") (pin "3") (pinfunction "S_3") (pintype "passive"))
    )
    (net (code "54") (name "Net-(I5-OUT3)") (class "Default")
      (node (ref "I5") (pin "5") (pinfunction "OUT3_5") (pintype "bidirectional"))
      (node (ref "X2") (pin "4") (pinfunction "S_4") (pintype "passive"))
    )
    (net (code "55") (name "Net-(I5-OUT4)") (class "Default")
      (node (ref "I5") (pin "8") (pinfunction "OUT4_8") (pintype "bidirectional"))
      (node (ref "X2") (pin "5") (pinfunction "S_5") (pintype "passive"))
    )
    (net (code "56") (name "Net-(I5-OUT5)") (class "Default")
      (node (ref "I5") (pin "9") (pinfunction "OUT5_9") (pintype "bidirectional"))
      (node (ref "X2") (pin "6") (pinfunction "S_6") (pintype "passive"))
    )
    (net (code "57") (name "Net-(I5-OUT6)") (class "Default")
      (node (ref "I5") (pin "10") (pinfunction "OUT6_10") (pintype "bidirectional"))
      (node (ref "X2") (pin "7") (pinfunction "S_7") (pintype "passive"))
    )
    (net (code "58") (name "Net-(I6-VIN+)") (class "Default")
      (node (ref "I6") (pin "3") (pinfunction "VIN+_3") (pintype "bidirectional"))
      (node (ref "J1") (pin "1") (pinfunction "1_1") (pintype "passive"))
      (node (ref "R26") (pin "2") (pinfunction "2_2") (pintype "passive"))
    )
    (net (code "59") (name "Net-(IC1-USBDM)") (class "Default")
      (node (ref "IC1") (pin "7") (pinfunction "USBDM_7") (pintype "input"))
      (node (ref "R2") (pin "2") (pinfunction "2_2") (pintype "passive"))
    )
    (net (code "60") (name "Net-(IC1-USBDP)") (class "Default")
      (node (ref "IC1") (pin "6") (pinfunction "USBDP_6") (pintype "input"))
      (node (ref "R1") (pin "2") (pinfunction "2_2") (pintype "passive"))
    )
    (net (code "61") (name "Net-(R-Pad2)") (class "Default")
      (node (ref "R") (pin "2") (pinfunction "2_2") (pintype "passive"))
      (node (ref "T1") (pin "S") (pinfunction "S_S") (pintype "bidirectional"))
      (node (ref "T2") (pin "S") (pinfunction "S_S") (pintype "bidirectional"))
      (node (ref "T3") (pin "S") (pinfunction "S_S") (pintype "bidirectional"))
      (node (ref "T4") (pin "S") (pinfunction "S_S") (pintype "bidirectional"))
      (node (ref "T5") (pin "S") (pinfunction "S_S") (pintype "bidirectional"))
    )
    (net (code "62") (name "Net-(R18-1)") (class "Default")
      (node (ref "R18") (pin "P$1") (pinfunction "1_P$1") (pintype "passive"))
      (node (ref "T1") (pin "D") (pinfunction "D_D") (pintype "bidirectional"))
    )
    (net (code "63") (name "Net-(R19-1)") (class "Default")
      (node (ref "R19") (pin "P$1") (pinfunction "1_P$1") (pintype "passive"))
      (node (ref "T2") (pin "D") (pinfunction "D_D") (pintype "bidirectional"))
    )
    (net (code "64") (name "Net-(R20-1)") (class "Default")
      (node (ref "R20") (pin "P$1") (pinfunction "1_P$1") (pintype "passive"))
      (node (ref "T3") (pin "D") (pinfunction "D_D") (pintype "bidirectional"))
    )
    (net (code "65") (name "Net-(R22-1)") (class "Default")
      (node (ref "R22") (pin "P$1") (pinfunction "1_P$1") (pintype "passive"))
      (node (ref "T4") (pin "D") (pinfunction "D_D") (pintype "bidirectional"))
    )
    (net (code "66") (name "Net-(R23-1)") (class "Default")
      (node (ref "R23") (pin "P$1") (pinfunction "1_P$1") (pintype "passive"))
      (node (ref "T5") (pin "D") (pinfunction "D_D") (pintype "bidirectional"))
    )
    (net (code "67") (name "Net-(R24-1)") (class "Default")
      (node (ref "R24") (pin "P$1") (pinfunction "1_P$1") (pintype "passive"))
      (node (ref "T6") (pin "D") (pinfunction "D_D") (pintype "bidirectional"))
    )
    (net (code "68") (name "Net-(R28-1)") (class "Default")
      (node (ref "R28") (pin "P$1") (pinfunction "1_P$1") (pintype "passive"))
      (node (ref "T7") (pin "D") (pinfunction "D_D") (pintype "bidirectional"))
    )
    (net (code "69") (name "Net-(R31-1)") (class "Default")
      (node (ref "R31") (pin "P$1") (pinfunction "1_P$1") (pintype "passive"))
      (node (ref "T8") (pin "D") (pinfunction "D_D") (pintype "bidirectional"))
    )
    (net (code "70") (name "Net-(U1-READY)") (class "Default")
      (node (ref "R13") (pin "1") (pinfunction "1_1") (pintype "passive"))
      (node (ref "U1") (pin "5") (pinfunction "READY_5") (pintype "bidirectional"))
    )
    (net (code "71") (name "unconnected-(CN1-PadID)") (class "Default")
      (node (ref "CN1") (pin "ID") (pinfunction "ID_ID") (pintype "bidirectional"))
    )
    (net (code "72") (name "unconnected-(I4-ADC6-Pad19)") (class "Default")
      (node (ref "I4") (pin "19") (pinfunction "ADC6_19") (pintype "bidirectional"))
    )
    (net (code "73") (name "unconnected-(I4-ADC7-Pad22)") (class "Default")
      (node (ref "I4") (pin "22") (pinfunction "ADC7_22") (pintype "bidirectional"))
    )
    (net (code "74") (name "unconnected-(I4-AREF-Pad20)") (class "Default")
      (node (ref "I4") (pin "20") (pinfunction "AREF_20") (pintype "bidirectional"))
    )
    (net (code "75") (name "unconnected-(I5-OUT7-Pad11)") (class "Default")
      (node (ref "I5") (pin "11") (pinfunction "OUT7_11") (pintype "bidirectional"))
    )
    (net (code "76") (name "unconnected-(I5-REF-Pad1)") (class "Default")
      (node (ref "I5") (pin "1") (pinfunction "REF_1") (pintype "bidirectional"))
    )
    (net (code "77") (name "unconnected-(IC1-CBUS0-Pad12)") (class "Default")
      (node (ref "IC1") (pin "12") (pinfunction "CBUS0_12") (pintype "bidirectional"))
    )
    (net (code "78") (name "unconnected-(IC1-CBUS1-Pad11)") (class "Default")
      (node (ref "IC1") (pin "11") (pinfunction "CBUS1_11") (pintype "bidirectional"))
    )
    (net (code "79") (name "unconnected-(IC1-CBUS2-Pad5)") (class "Default")
      (node (ref "IC1") (pin "5") (pinfunction "CBUS2_5") (pintype "bidirectional"))
    )
    (net (code "80") (name "unconnected-(IC1-CBUS3-Pad14)") (class "Default")
      (node (ref "IC1") (pin "14") (pinfunction "CBUS3_14") (pintype "bidirectional"))
    )
    (net (code "81") (name "unconnected-(IC1-~{CTS}-Pad4)") (class "Default")
      (node (ref "IC1") (pin "4") (pinfunction "~{CTS}_4") (pintype "input"))
    )
    (net (code "82") (name "unconnected-(IC1-~{RTS}-Pad16)") (class "Default")
      (node (ref "IC1") (pin "16") (pinfunction "~{RTS}_16") (pintype "output"))
    )
    (net (code "83") (name "unconnected-(SPACER1-Pad1)") (class "Default")
      (node (ref "SPACER1") (pin "1") (pinfunction "1_1") (pintype "passive"))
    )
    (net (code "84") (name "unconnected-(SPACER2-Pad1)") (class "Default")
      (node (ref "SPACER2") (pin "1") (pinfunction "1_1") (pintype "passive"))
    )
    (net (code "85") (name "unconnected-(SPACER3-Pad1)") (class "Default")
      (node (ref "SPACER3") (pin "1") (pinfunction "1_1") (pintype "passive"))
    )
    (net (code "86") (name "unconnected-(SPACER4-Pad1)") (class "Default")
      (node (ref "SPACER4") (pin "1") (pinfunction "1_1") (pintype "passive"))
    )
  )
)
